# Altimeter-Barometer.net
KiCad netlist of a schematic drawn in EAGLE
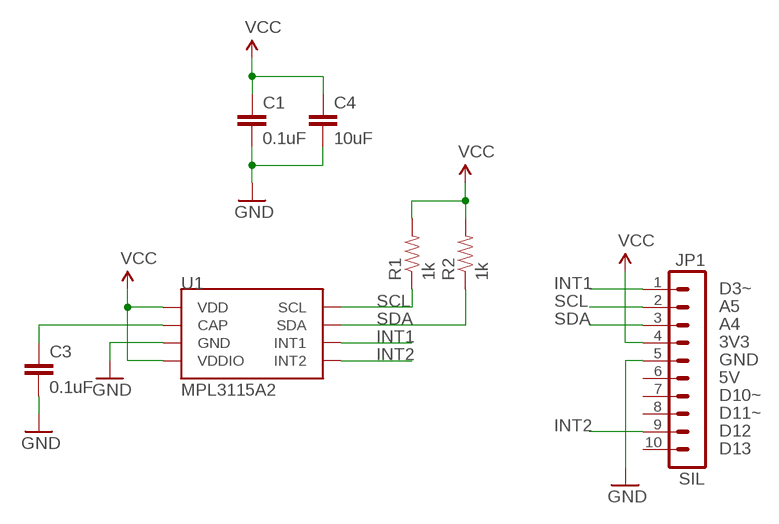
[diagram p0: schematic, sheet 1]

(export (version "E")
  (design (tool "Eeschema 10.0.6"))
  (components
    (comp (ref "C1")
      (value "0.1uF")
      (footprint "eagle-import:0603-CAP")
      (libsource (lib "eagle-import") (part "CAP0603-CAP"))
    )
    (comp (ref "C3")
      (value "0.1uF")
      (footprint "eagle-import:0603-CAP")
      (libsource (lib "eagle-import") (part "CAP0603-CAP"))
    )
    (comp (ref "C4")
      (value "10uF")
      (footprint "eagle-import:0805")
      (libsource (lib "eagle-import") (part "22UF-6.3V-20%(0805)"))
    )
    (comp (ref "JP1")
      (value "SIL")
      (footprint "eagle-import:SIL-1X10")
      (fields (field (name "MANUFACTURER") "FCI") (field (name "PART_NUMBER") "77315-818-36LF "))
      (libsource (lib "eagle-import") (part "1X10-SIL-CONNECTOR"))
    )
    (comp (ref "R1")
      (value "1k")
      (footprint "eagle-import:0603-RES")
      (libsource (lib "eagle-import") (part "RESISTOR0603-RES"))
    )
    (comp (ref "R2")
      (value "1k")
      (footprint "eagle-import:0603-RES")
      (libsource (lib "eagle-import") (part "RESISTOR0603-RES"))
    )
    (comp (ref "U1")
      (value "MPL3115A2")
      (footprint "eagle-import:LGA8")
      (libsource (lib "eagle-import") (part "MPL3115A2LGA8"))
    )
  )
  (nets
    (net (code "1") (name "/INT1") (class "Default")
      (node (ref "JP1") (pin "1") (pinfunction "1_1") (pintype "passive"))
      (node (ref "U1") (pin "6") (pinfunction "INT1_6") (pintype "output"))
    )
    (net (code "2") (name "/INT2") (class "Default")
      (node (ref "JP1") (pin "9") (pinfunction "9_9") (pintype "passive"))
      (node (ref "U1") (pin "5") (pinfunction "INT2_5") (pintype "output"))
    )
    (net (code "3") (name "/SCL") (class "Default")
      (node (ref "JP1") (pin "2") (pinfunction "2_2") (pintype "passive"))
      (node (ref "R1") (pin "1") (pinfunction "1_1") (pintype "passive"))
      (node (ref "U1") (pin "8") (pinfunction "SCL_8") (pintype "bidirectional"))
    )
    (net (code "4") (name "/SDA") (class "Default")
      (node (ref "JP1") (pin "3") (pinfunction "3_3") (pintype "passive"))
      (node (ref "R2") (pin "1") (pinfunction "1_1") (pintype "passive"))
      (node (ref "U1") (pin "7") (pinfunction "SDA_7") (pintype "bidirectional"))
    )
    (net (code "5") (name "GND") (class "Default")
      (node (ref "C1") (pin "2") (pinfunction "2_2") (pintype "passive"))
      (node (ref "C3") (pin "2") (pinfunction "2_2") (pintype "passive"))
      (node (ref "C4") (pin "2") (pinfunction "2_2") (pintype "passive"))
      (node (ref "JP1") (pin "5") (pinfunction "5_5") (pintype "passive"))
      (node (ref "U1") (pin "3") (pinfunction "GND_3") (pintype "power_in"))
    )
    (net (code "6") (name "Net-(U1-CAP)") (class "Default")
      (node (ref "C3") (pin "1") (pinfunction "1_1") (pintype "passive"))
      (node (ref "U1") (pin "2") (pinfunction "CAP_2") (pintype "power_in"))
    )
    (net (code "7") (name "VCC") (class "Default")
      (node (ref "C1") (pin "1") (pinfunction "1_1") (pintype "passive"))
      (node (ref "C4") (pin "1") (pinfunction "1_1") (pintype "passive"))
      (node (ref "JP1") (pin "4") (pinfunction "4_4") (pintype "passive"))
      (node (ref "R1") (pin "2") (pinfunction "2_2") (pintype "passive"))
      (node (ref "R2") (pin "2") (pinfunction "2_2") (pintype "passive"))
      (node (ref "U1") (pin "1") (pinfunction "VDD_1") (pintype "power_in"))
      (node (ref "U1") (pin "4") (pinfunction "VDDIO_4") (pintype "power_in"))
    )
    (net (code "8") (name "unconnected-(JP1-Pad6)") (class "Default")
      (node (ref "JP1") (pin "6") (pinfunction "6_6") (pintype "passive"))
    )
    (net (code "9") (name "unconnected-(JP1-Pad7)") (class "Default")
      (node (ref "JP1") (pin "7") (pinfunction "7_7") (pintype "passive"))
    )
    (net (code "10") (name "unconnected-(JP1-Pad8)") (class "Default")
      (node (ref "JP1") (pin "8") (pinfunction "8_8") (pintype "passive"))
    )
    (net (code "11") (name "unconnected-(JP1-Pad10)") (class "Default")
      (node (ref "JP1") (pin "10") (pinfunction "10_10") (pintype "passive"))
    )
  )
)
